# MiniSat_Sensors_main.net
KiCad netlist of a schematic drawn in Altium Designer
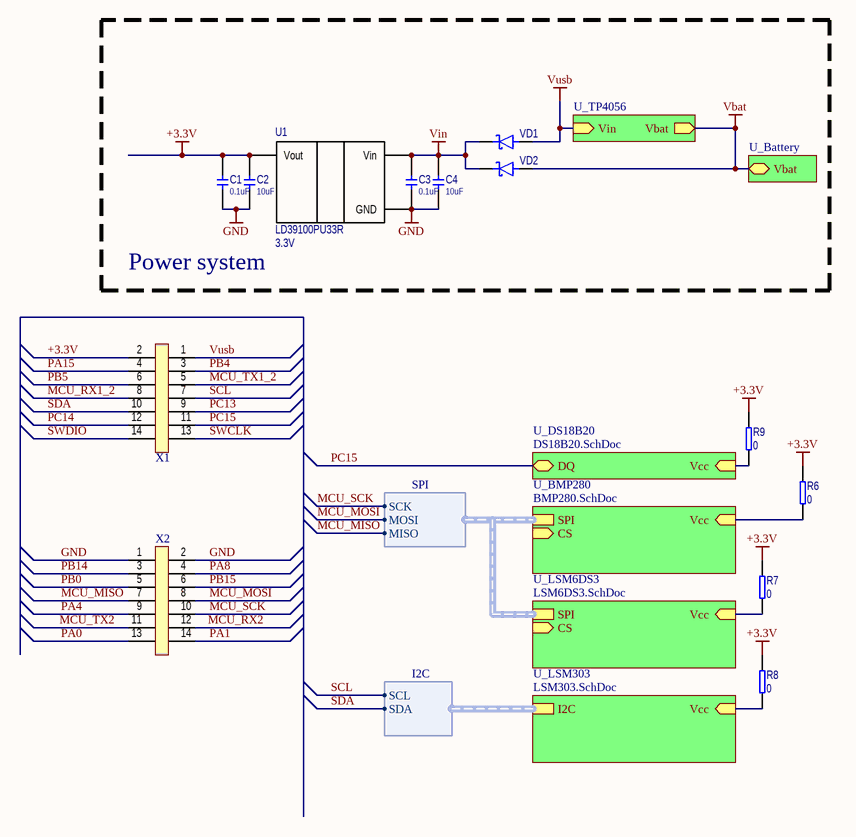
[diagram p0: MiniSat_Sensors_main.SchDoc]

(export (version "E")
  (design (tool "Eeschema 10.0.6"))
  (components
    (comp (ref "C1")
      (value "0.1uF")
      (footprint "CERCAP 0402")
      (description "Capacitor")
      (fields (field (name "Comment") "CERCAP 0402 0.1uF * X7R"))
      (libsource (lib "!main") (part "!Capacitor"))
    )
    (comp (ref "C2")
      (value "10uF")
      (footprint "CERCAP 0603")
      (description "Capacitor")
      (fields (field (name "Comment") "CERCAP 0603 10uF * X7R"))
      (libsource (lib "!main") (part "!Capacitor"))
    )
    (comp (ref "C3")
      (value "0.1uF")
      (footprint "CERCAP 0402")
      (description "Capacitor")
      (fields (field (name "Comment") "CERCAP 0402 0.1uF * X7R"))
      (libsource (lib "!main") (part "!Capacitor"))
    )
    (comp (ref "C4")
      (value "10uF")
      (footprint "CERCAP 0603")
      (description "Capacitor")
      (fields (field (name "Comment") "CERCAP 0603 10uF * X7R"))
      (libsource (lib "!main") (part "!Capacitor"))
    )
    (comp (ref "R6")
      (value "0")
      (footprint "RES 0402")
      (description "Resistor")
      (fields (field (name "Comment") "RES 0402 0"))
      (libsource (lib "!main") (part "!Resistor"))
    )
    (comp (ref "R7")
      (value "0")
      (footprint "RES 0402")
      (description "Resistor")
      (fields (field (name "Comment") "RES 0402 0"))
      (libsource (lib "!main") (part "!Resistor"))
    )
    (comp (ref "R8")
      (value "0")
      (footprint "RES 0402")
      (description "Resistor")
      (fields (field (name "Comment") "RES 0402 0"))
      (libsource (lib "!main") (part "!Resistor"))
    )
    (comp (ref "R9")
      (value "0")
      (footprint "RES 0402")
      (description "Resistor")
      (fields (field (name "Comment") "RES 0402 0"))
      (libsource (lib "!main") (part "!Resistor"))
    )
    (comp (ref "U1")
      (value "LD39100PU33R")
      (footprint "DFN-6")
      (description "generic ldo")
      (fields (field (name "ALTIUM_VALUE") "3.3V"))
      (libsource (lib "power") (part "!Generic LDO"))
    )
    (comp (ref "VD1")
      (value "Shottly diode SOD-123")
      (footprint "SOD-123")
      (description "Diode Shottky")
      (libsource (lib "diodes") (part "DiodeS"))
    )
    (comp (ref "VD2")
      (value "Shottly diode SOD-123")
      (footprint "SOD-123")
      (description "Diode Shottky")
      (libsource (lib "diodes") (part "DiodeS"))
    )
    (comp (ref "X1")
      (value "Header")
      (footprint "PC-14_A")
      (description "7x2 header")
      (libsource (lib "") (part "Header 7x2_1"))
    )
    (comp (ref "X2")
      (value "Header")
      (footprint "PC-14_A")
      (description "7x2 header")
      (libsource (lib "AltTab_LIBSCH_Connectors") (part "Header 7x2"))
    )
  )
  (nets
    (net (code "3") (name "+3.3V") (class "Default")
      (node (ref "C1") (pin "2") (pintype "passive"))
      (node (ref "C2") (pin "2") (pintype "passive"))
      (node (ref "R6") (pin "2") (pinfunction "12_2") (pintype "passive"))
      (node (ref "R7") (pin "2") (pinfunction "12_2") (pintype "passive"))
      (node (ref "R8") (pin "2") (pinfunction "12_2") (pintype "passive"))
      (node (ref "R9") (pin "2") (pinfunction "12_2") (pintype "passive"))
      (node (ref "U1") (pin "Vout") (pinfunction "Vout_Vout") (pintype "passive"))
      (node (ref "X1") (pin "2") (pintype "passive"))
    )
    (net (code "6") (name "/MCU_MISO") (class "Default") (node (ref "X2") (pin "7") (pintype "passive")))
    (net (code "7") (name "/MCU_MOSI") (class "Default") (node (ref "X2") (pin "8") (pintype "passive")))
    (net (code "8") (name "/MCU_RX1_2") (class "Default") (node (ref "X1") (pin "8") (pintype "passive")))
    (net (code "9") (name "/MCU_RX2") (class "Default") (node (ref "X2") (pin "12") (pintype "passive")))
    (net (code "10") (name "/MCU_SCK") (class "Default") (node (ref "X2") (pin "10") (pintype "passive")))
    (net (code "11") (name "/MCU_TX1_2") (class "Default") (node (ref "X1") (pin "5") (pintype "passive")))
    (net (code "12") (name "/MCU_TX2") (class "Default") (node (ref "X2") (pin "11") (pintype "passive")))
    (net (code "13") (name "/PA0") (class "Default") (node (ref "X2") (pin "13") (pintype "passive")))
    (net (code "14") (name "/PA1") (class "Default") (node (ref "X2") (pin "14") (pintype "passive")))
    (net (code "15") (name "/PA4") (class "Default") (node (ref "X2") (pin "9") (pintype "passive")))
    (net (code "16") (name "/PA8") (class "Default") (node (ref "X2") (pin "4") (pintype "passive")))
    (net (code "17") (name "/PA15") (class "Default") (node (ref "X1") (pin "4") (pintype "passive")))
    (net (code "18") (name "/PB0") (class "Default") (node (ref "X2") (pin "5") (pintype "passive")))
    (net (code "19") (name "/PB4") (class "Default") (node (ref "X1") (pin "3") (pintype "passive")))
    (net (code "20") (name "/PB5") (class "Default") (node (ref "X1") (pin "6") (pintype "passive")))
    (net (code "21") (name "/PB14") (class "Default") (node (ref "X2") (pin "3") (pintype "passive")))
    (net (code "22") (name "/PB15") (class "Default") (node (ref "X2") (pin "6") (pintype "passive")))
    (net (code "23") (name "/PC13") (class "Default") (node (ref "X1") (pin "9") (pintype "passive")))
    (net (code "24") (name "/PC14") (class "Default") (node (ref "X1") (pin "12") (pintype "passive")))
    (net (code "25") (name "/PC15") (class "Default") (node (ref "X1") (pin "11") (pintype "passive")))
    (net (code "26") (name "/SCL") (class "Default") (node (ref "X1") (pin "7") (pintype "passive")))
    (net (code "27") (name "/SDA") (class "Default") (node (ref "X1") (pin "10") (pintype "passive")))
    (net (code "28") (name "/SWCLK") (class "Default") (node (ref "X1") (pin "13") (pintype "passive")))
    (net (code "29") (name "/SWDIO") (class "Default") (node (ref "X1") (pin "14") (pintype "passive")))
    (net (code "30") (name "/Vcc") (class "Default")
      (node (ref "R6") (pin "1") (pinfunction "11_1") (pintype "passive"))
    )
    (net (code "31") (name "/Vcc_1") (class "Default")
      (node (ref "R9") (pin "1") (pinfunction "11_1") (pintype "passive"))
    )
    (net (code "32") (name "/Vcc_2") (class "Default")
      (node (ref "R8") (pin "1") (pinfunction "11_1") (pintype "passive"))
    )
    (net (code "33") (name "/Vcc_3") (class "Default")
      (node (ref "R7") (pin "1") (pinfunction "11_1") (pintype "passive"))
    )
    (net (code "36") (name "GND") (class "Default")
      (node (ref "C1") (pin "1") (pintype "passive"))
      (node (ref "C2") (pin "1") (pintype "passive"))
      (node (ref "C3") (pin "1") (pintype "passive"))
      (node (ref "C4") (pin "1") (pintype "passive"))
      (node (ref "U1") (pin "ADJ/GND") (pinfunction "GND_ADJ/GND") (pintype "passive"))
      (node (ref "X2") (pin "1") (pintype "passive"))
      (node (ref "X2") (pin "2") (pintype "passive"))
    )
    (net (code "37") (name "Vbat") (class "Default")
      (node (ref "VD2") (pin "A") (pinfunction "Anode_A") (pintype "passive"))
    )
    (net (code "38") (name "Vin") (class "Default")
      (node (ref "C3") (pin "2") (pintype "passive"))
      (node (ref "C4") (pin "2") (pintype "passive"))
      (node (ref "U1") (pin "Vin") (pinfunction "Vin_Vin") (pintype "passive"))
      (node (ref "VD1") (pin "C") (pinfunction "Cathode_C") (pintype "passive"))
      (node (ref "VD2") (pin "C") (pinfunction "Cathode_C") (pintype "passive"))
    )
    (net (code "39") (name "Vusb") (class "Default")
      (node (ref "VD1") (pin "A") (pinfunction "Anode_A") (pintype "passive"))
      (node (ref "X1") (pin "1") (pintype "passive"))
    )
  )
)
